# Sudden_XCVR_Mic_Amp.net
KiCad netlist of a schematic drawn in EAGLE
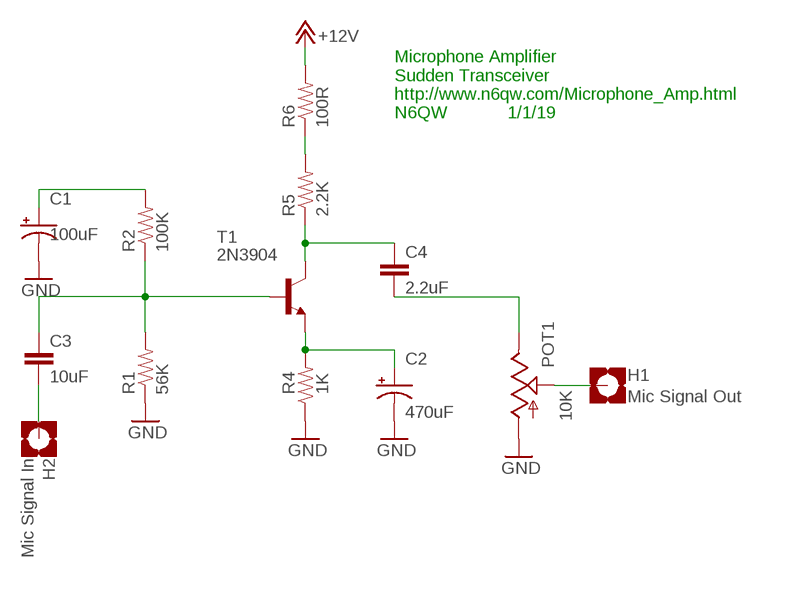
[diagram p0: schematic, sheet 1]

(export (version "E")
  (design (tool "Eeschema 10.0.6"))
  (components
    (comp (ref "C1")
      (value "100uF")
      (footprint "eagle-import:CAP-POLARIZED")
      (libsource (lib "eagle-import") (part "CAP-POLARIZED-RADIAL-2.5MM-25V-20%"))
    )
    (comp (ref "C2")
      (value "470uF")
      (footprint "eagle-import:CAP-POLARIZED")
      (libsource (lib "eagle-import") (part "CAP-POLARIZED-RADIAL-2.5MM-25V-20%"))
    )
    (comp (ref "C3")
      (value "10uF")
      (footprint "eagle-import:CAP-MEDIUM-MUPPET")
      (libsource (lib "eagle-import") (part "CAP-MEDIUM-MUPPET"))
    )
    (comp (ref "C4")
      (value "2.2uF")
      (footprint "eagle-import:CAP-MEDIUM-MUPPET")
      (libsource (lib "eagle-import") (part "CAP-MEDIUM-MUPPET"))
    )
    (comp (ref "H1")
      (value "Mic Signal Out")
      (footprint "eagle-import:PAD-SQUARE")
      (libsource (lib "eagle-import") (part "MOUNT-PAD-SQUARE4.5"))
    )
    (comp (ref "H2")
      (value "Mic Signal In")
      (footprint "eagle-import:PAD-SQUARE")
      (libsource (lib "eagle-import") (part "MOUNT-PAD-SQUARE4.5"))
    )
    (comp (ref "P+1")
      (value "+12V")
      (footprint "eagle-import:POWER-IN-PAD")
      (libsource (lib "eagle-import") (part "+12V"))
    )
    (comp (ref "POT1")
      (value "10K")
      (footprint "eagle-import:POT-TRIMM-4")
      (libsource (lib "eagle-import") (part "POTENTIOMETER-TRIMCT6"))
    )
    (comp (ref "R1")
      (value "56K")
      (footprint "eagle-import:RESITOR-MUPPET")
      (libsource (lib "eagle-import") (part "RESISTOR-MUPPETMEDIUM-RESISTOR-PADS"))
    )
    (comp (ref "R2")
      (value "100K")
      (footprint "eagle-import:RESITOR-MUPPET")
      (libsource (lib "eagle-import") (part "RESISTOR-MUPPETMEDIUM-RESISTOR-PADS"))
    )
    (comp (ref "R4")
      (value "1K")
      (footprint "eagle-import:RESITOR-MUPPET")
      (libsource (lib "eagle-import") (part "RESISTOR-MUPPETMEDIUM-RESISTOR-PADS"))
    )
    (comp (ref "R5")
      (value "2.2K")
      (footprint "eagle-import:RESITOR-MUPPET")
      (libsource (lib "eagle-import") (part "RESISTOR-MUPPETMEDIUM-RESISTOR-PADS"))
    )
    (comp (ref "R6")
      (value "100R")
      (footprint "eagle-import:RESITOR-MUPPET")
      (libsource (lib "eagle-import") (part "RESISTOR-MUPPETMEDIUM-RESISTOR-PADS"))
    )
    (comp (ref "T1")
      (value "2N3904")
      (footprint "eagle-import:TO92")
      (libsource (lib "eagle-import") (part "2N3904"))
    )
  )
  (nets
    (net (code "1") (name "+12V") (class "Default")
      (node (ref "P+1") (pin "VCC") (pinfunction "+12V_VCC") (pintype "power_in"))
      (node (ref "R6") (pin "P$2") (pinfunction "2_P$2") (pintype "passive"))
    )
    (net (code "2") (name "GND") (class "Default")
      (node (ref "C1") (pin "2") (pinfunction "-_2") (pintype "passive"))
      (node (ref "C2") (pin "2") (pinfunction "-_2") (pintype "passive"))
      (node (ref "POT1") (pin "A") (pinfunction "A_A") (pintype "passive"))
      (node (ref "R1") (pin "P$1") (pinfunction "1_P$1") (pintype "passive"))
      (node (ref "R4") (pin "P$1") (pinfunction "1_P$1") (pintype "passive"))
    )
    (net (code "3") (name "Net-(C1-+)") (class "Default")
      (node (ref "C1") (pin "1") (pinfunction "+_1") (pintype "passive"))
      (node (ref "R2") (pin "P$2") (pinfunction "2_P$2") (pintype "passive"))
    )
    (net (code "4") (name "Net-(C2-+)") (class "Default")
      (node (ref "C2") (pin "1") (pinfunction "+_1") (pintype "passive"))
      (node (ref "R4") (pin "P$2") (pinfunction "2_P$2") (pintype "passive"))
      (node (ref "T1") (pin "3") (pinfunction "E_3") (pintype "passive"))
    )
    (net (code "5") (name "Net-(C4-Pad2)") (class "Default")
      (node (ref "C4") (pin "2") (pinfunction "2_2") (pintype "passive"))
      (node (ref "POT1") (pin "E") (pinfunction "E_E") (pintype "passive"))
    )
    (net (code "6") (name "Net-(H1-MOUNT)") (class "Default")
      (node (ref "H1") (pin "PAD") (pinfunction "MOUNT_PAD") (pintype "passive"))
      (node (ref "POT1") (pin "S") (pinfunction "S_S") (pintype "passive"))
    )
    (net (code "7") (name "Net-(H2-MOUNT)") (class "Default")
      (node (ref "C3") (pin "2") (pinfunction "2_2") (pintype "passive"))
      (node (ref "H2") (pin "PAD") (pinfunction "MOUNT_PAD") (pintype "passive"))
    )
    (net (code "8") (name "Net-(R1-2)") (class "Default")
      (node (ref "C3") (pin "1") (pinfunction "1_1") (pintype "passive"))
      (node (ref "R1") (pin "P$2") (pinfunction "2_P$2") (pintype "passive"))
      (node (ref "R2") (pin "P$1") (pinfunction "1_P$1") (pintype "passive"))
      (node (ref "T1") (pin "2") (pinfunction "B_2") (pintype "passive"))
    )
    (net (code "9") (name "Net-(R5-1)") (class "Default")
      (node (ref "C4") (pin "1") (pinfunction "1_1") (pintype "passive"))
      (node (ref "R5") (pin "P$1") (pinfunction "1_P$1") (pintype "passive"))
      (node (ref "T1") (pin "1") (pinfunction "C_1") (pintype "passive"))
    )
    (net (code "10") (name "Net-(R5-2)") (class "Default")
      (node (ref "R5") (pin "P$2") (pinfunction "2_P$2") (pintype "passive"))
      (node (ref "R6") (pin "P$1") (pinfunction "1_P$1") (pintype "passive"))
    )
  )
)
